# x50_brakelight.net
KiCad netlist of a schematic drawn in EAGLE
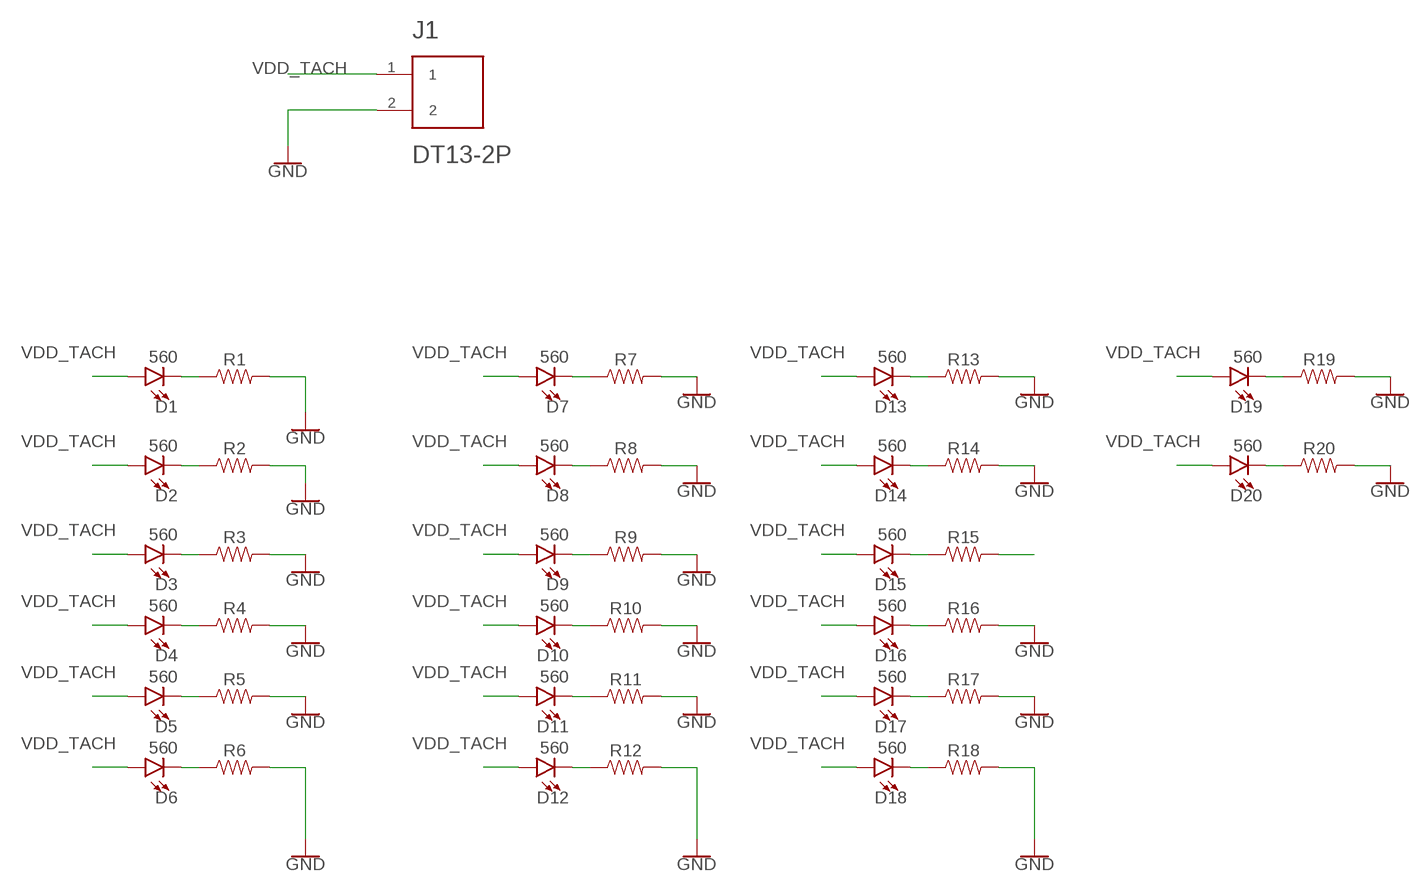
[diagram p0: schematic, sheet 1]

(export (version "E")
  (design (tool "Eeschema 10.0.6"))
  (components
    (comp (ref "D1")
      (value "560")
      (footprint "eagle-import:LED_5MM")
      (libsource (lib "eagle-import") (part "LED5MM"))
    )
    (comp (ref "D2")
      (value "560")
      (footprint "eagle-import:LED_5MM")
      (libsource (lib "eagle-import") (part "LED5MM"))
    )
    (comp (ref "D3")
      (value "560")
      (footprint "eagle-import:LED_5MM")
      (libsource (lib "eagle-import") (part "LED5MM"))
    )
    (comp (ref "D4")
      (value "560")
      (footprint "eagle-import:LED_5MM")
      (libsource (lib "eagle-import") (part "LED5MM"))
    )
    (comp (ref "D5")
      (value "560")
      (footprint "eagle-import:LED_5MM")
      (libsource (lib "eagle-import") (part "LED5MM"))
    )
    (comp (ref "D6")
      (value "560")
      (footprint "eagle-import:LED_5MM")
      (libsource (lib "eagle-import") (part "LED5MM"))
    )
    (comp (ref "D7")
      (value "560")
      (footprint "eagle-import:LED_5MM")
      (libsource (lib "eagle-import") (part "LED5MM"))
    )
    (comp (ref "D8")
      (value "560")
      (footprint "eagle-import:LED_5MM")
      (libsource (lib "eagle-import") (part "LED5MM"))
    )
    (comp (ref "D9")
      (value "560")
      (footprint "eagle-import:LED_5MM")
      (libsource (lib "eagle-import") (part "LED5MM"))
    )
    (comp (ref "D10")
      (value "560")
      (footprint "eagle-import:LED_5MM")
      (libsource (lib "eagle-import") (part "LED5MM"))
    )
    (comp (ref "D11")
      (value "560")
      (footprint "eagle-import:LED_5MM")
      (libsource (lib "eagle-import") (part "LED5MM"))
    )
    (comp (ref "D12")
      (value "560")
      (footprint "eagle-import:LED_5MM")
      (libsource (lib "eagle-import") (part "LED5MM"))
    )
    (comp (ref "D13")
      (value "560")
      (footprint "eagle-import:LED_5MM")
      (libsource (lib "eagle-import") (part "LED5MM"))
    )
    (comp (ref "D14")
      (value "560")
      (footprint "eagle-import:LED_5MM")
      (libsource (lib "eagle-import") (part "LED5MM"))
    )
    (comp (ref "D15")
      (value "560")
      (footprint "eagle-import:LED_5MM")
      (libsource (lib "eagle-import") (part "LED5MM"))
    )
    (comp (ref "D16")
      (value "560")
      (footprint "eagle-import:LED_5MM")
      (libsource (lib "eagle-import") (part "LED5MM"))
    )
    (comp (ref "D17")
      (value "560")
      (footprint "eagle-import:LED_5MM")
      (libsource (lib "eagle-import") (part "LED5MM"))
    )
    (comp (ref "D18")
      (value "560")
      (footprint "eagle-import:LED_5MM")
      (libsource (lib "eagle-import") (part "LED5MM"))
    )
    (comp (ref "D19")
      (value "560")
      (footprint "eagle-import:LED_5MM")
      (libsource (lib "eagle-import") (part "LED5MM"))
    )
    (comp (ref "D20")
      (value "560")
      (footprint "eagle-import:LED_5MM")
      (libsource (lib "eagle-import") (part "LED5MM"))
    )
    (comp (ref "J1")
      (value "DT13-2P")
      (footprint "eagle-import:TE_DT13-2P")
      (fields (field (name "MF") "TE Connectivity") (field (name "MPN") "DT13-2P "))
      (libsource (lib "eagle-import") (part "DT13-2P"))
    )
    (comp (ref "R1")
      (value "RESISTORAXIAL-0.3")
      (footprint "eagle-import:AXIAL-0.3")
      (libsource (lib "eagle-import") (part "RESISTORAXIAL-0.3"))
    )
    (comp (ref "R2")
      (value "RESISTORAXIAL-0.3")
      (footprint "eagle-import:AXIAL-0.3")
      (libsource (lib "eagle-import") (part "RESISTORAXIAL-0.3"))
    )
    (comp (ref "R3")
      (value "RESISTORAXIAL-0.3")
      (footprint "eagle-import:AXIAL-0.3")
      (libsource (lib "eagle-import") (part "RESISTORAXIAL-0.3"))
    )
    (comp (ref "R4")
      (value "RESISTORAXIAL-0.3")
      (footprint "eagle-import:AXIAL-0.3")
      (libsource (lib "eagle-import") (part "RESISTORAXIAL-0.3"))
    )
    (comp (ref "R5")
      (value "RESISTORAXIAL-0.3")
      (footprint "eagle-import:AXIAL-0.3")
      (libsource (lib "eagle-import") (part "RESISTORAXIAL-0.3"))
    )
    (comp (ref "R6")
      (value "RESISTORAXIAL-0.3")
      (footprint "eagle-import:AXIAL-0.3")
      (libsource (lib "eagle-import") (part "RESISTORAXIAL-0.3"))
    )
    (comp (ref "R7")
      (value "RESISTORAXIAL-0.3")
      (footprint "eagle-import:AXIAL-0.3")
      (libsource (lib "eagle-import") (part "RESISTORAXIAL-0.3"))
    )
    (comp (ref "R8")
      (value "RESISTORAXIAL-0.3")
      (footprint "eagle-import:AXIAL-0.3")
      (libsource (lib "eagle-import") (part "RESISTORAXIAL-0.3"))
    )
    (comp (ref "R9")
      (value "RESISTORAXIAL-0.3")
      (footprint "eagle-import:AXIAL-0.3")
      (libsource (lib "eagle-import") (part "RESISTORAXIAL-0.3"))
    )
    (comp (ref "R10")
      (value "RESISTORAXIAL-0.3")
      (footprint "eagle-import:AXIAL-0.3")
      (libsource (lib "eagle-import") (part "RESISTORAXIAL-0.3"))
    )
    (comp (ref "R11")
      (value "RESISTORAXIAL-0.3")
      (footprint "eagle-import:AXIAL-0.3")
      (libsource (lib "eagle-import") (part "RESISTORAXIAL-0.3"))
    )
    (comp (ref "R12")
      (value "RESISTORAXIAL-0.3")
      (footprint "eagle-import:AXIAL-0.3")
      (libsource (lib "eagle-import") (part "RESISTORAXIAL-0.3"))
    )
    (comp (ref "R13")
      (value "RESISTORAXIAL-0.3")
      (footprint "eagle-import:AXIAL-0.3")
      (libsource (lib "eagle-import") (part "RESISTORAXIAL-0.3"))
    )
    (comp (ref "R14")
      (value "RESISTORAXIAL-0.3")
      (footprint "eagle-import:AXIAL-0.3")
      (libsource (lib "eagle-import") (part "RESISTORAXIAL-0.3"))
    )
    (comp (ref "R15")
      (value "RESISTORAXIAL-0.3")
      (footprint "eagle-import:AXIAL-0.3")
      (libsource (lib "eagle-import") (part "RESISTORAXIAL-0.3"))
    )
    (comp (ref "R16")
      (value "RESISTORAXIAL-0.3")
      (footprint "eagle-import:AXIAL-0.3")
      (libsource (lib "eagle-import") (part "RESISTORAXIAL-0.3"))
    )
    (comp (ref "R17")
      (value "RESISTORAXIAL-0.3")
      (footprint "eagle-import:AXIAL-0.3")
      (libsource (lib "eagle-import") (part "RESISTORAXIAL-0.3"))
    )
    (comp (ref "R18")
      (value "RESISTORAXIAL-0.3")
      (footprint "eagle-import:AXIAL-0.3")
      (libsource (lib "eagle-import") (part "RESISTORAXIAL-0.3"))
    )
    (comp (ref "R19")
      (value "RESISTORAXIAL-0.3")
      (footprint "eagle-import:AXIAL-0.3")
      (libsource (lib "eagle-import") (part "RESISTORAXIAL-0.3"))
    )
    (comp (ref "R20")
      (value "RESISTORAXIAL-0.3")
      (footprint "eagle-import:AXIAL-0.3")
      (libsource (lib "eagle-import") (part "RESISTORAXIAL-0.3"))
    )
  )
  (nets
    (net (code "1") (name "/VDD_TACH") (class "Default")
      (node (ref "D1") (pin "A") (pinfunction "A_A") (pintype "passive"))
      (node (ref "D10") (pin "A") (pinfunction "A_A") (pintype "passive"))
      (node (ref "D11") (pin "A") (pinfunction "A_A") (pintype "passive"))
      (node (ref "D12") (pin "A") (pinfunction "A_A") (pintype "passive"))
      (node (ref "D13") (pin "A") (pinfunction "A_A") (pintype "passive"))
      (node (ref "D14") (pin "A") (pinfunction "A_A") (pintype "passive"))
      (node (ref "D15") (pin "A") (pinfunction "A_A") (pintype "passive"))
      (node (ref "D16") (pin "A") (pinfunction "A_A") (pintype "passive"))
      (node (ref "D17") (pin "A") (pinfunction "A_A") (pintype "passive"))
      (node (ref "D18") (pin "A") (pinfunction "A_A") (pintype "passive"))
      (node (ref "D19") (pin "A") (pinfunction "A_A") (pintype "passive"))
      (node (ref "D2") (pin "A") (pinfunction "A_A") (pintype "passive"))
      (node (ref "D20") (pin "A") (pinfunction "A_A") (pintype "passive"))
      (node (ref "D3") (pin "A") (pinfunction "A_A") (pintype "passive"))
      (node (ref "D4") (pin "A") (pinfunction "A_A") (pintype "passive"))
      (node (ref "D5") (pin "A") (pinfunction "A_A") (pintype "passive"))
      (node (ref "D6") (pin "A") (pinfunction "A_A") (pintype "passive"))
      (node (ref "D7") (pin "A") (pinfunction "A_A") (pintype "passive"))
      (node (ref "D8") (pin "A") (pinfunction "A_A") (pintype "passive"))
      (node (ref "D9") (pin "A") (pinfunction "A_A") (pintype "passive"))
      (node (ref "J1") (pin "1") (pinfunction "1_1") (pintype "passive"))
    )
    (net (code "2") (name "GND") (class "Default")
      (node (ref "J1") (pin "2") (pinfunction "2_2") (pintype "passive"))
      (node (ref "R1") (pin "P$2") (pinfunction "2_P$2") (pintype "passive"))
      (node (ref "R10") (pin "P$2") (pinfunction "2_P$2") (pintype "passive"))
      (node (ref "R11") (pin "P$2") (pinfunction "2_P$2") (pintype "passive"))
      (node (ref "R12") (pin "P$2") (pinfunction "2_P$2") (pintype "passive"))
      (node (ref "R13") (pin "P$2") (pinfunction "2_P$2") (pintype "passive"))
      (node (ref "R14") (pin "P$2") (pinfunction "2_P$2") (pintype "passive"))
      (node (ref "R16") (pin "P$2") (pinfunction "2_P$2") (pintype "passive"))
      (node (ref "R17") (pin "P$2") (pinfunction "2_P$2") (pintype "passive"))
      (node (ref "R18") (pin "P$2") (pinfunction "2_P$2") (pintype "passive"))
      (node (ref "R19") (pin "P$2") (pinfunction "2_P$2") (pintype "passive"))
      (node (ref "R2") (pin "P$2") (pinfunction "2_P$2") (pintype "passive"))
      (node (ref "R20") (pin "P$2") (pinfunction "2_P$2") (pintype "passive"))
      (node (ref "R3") (pin "P$2") (pinfunction "2_P$2") (pintype "passive"))
      (node (ref "R4") (pin "P$2") (pinfunction "2_P$2") (pintype "passive"))
      (node (ref "R5") (pin "P$2") (pinfunction "2_P$2") (pintype "passive"))
      (node (ref "R6") (pin "P$2") (pinfunction "2_P$2") (pintype "passive"))
      (node (ref "R7") (pin "P$2") (pinfunction "2_P$2") (pintype "passive"))
      (node (ref "R8") (pin "P$2") (pinfunction "2_P$2") (pintype "passive"))
      (node (ref "R9") (pin "P$2") (pinfunction "2_P$2") (pintype "passive"))
    )
    (net (code "3") (name "Net-(D1-C)") (class "Default")
      (node (ref "D1") (pin "K") (pinfunction "C_K") (pintype "passive"))
      (node (ref "R1") (pin "P$1") (pinfunction "1_P$1") (pintype "passive"))
    )
    (net (code "4") (name "Net-(D2-C)") (class "Default")
      (node (ref "D2") (pin "K") (pinfunction "C_K") (pintype "passive"))
      (node (ref "R2") (pin "P$1") (pinfunction "1_P$1") (pintype "passive"))
    )
    (net (code "5") (name "Net-(D3-C)") (class "Default")
      (node (ref "D3") (pin "K") (pinfunction "C_K") (pintype "passive"))
      (node (ref "R3") (pin "P$1") (pinfunction "1_P$1") (pintype "passive"))
    )
    (net (code "6") (name "Net-(D4-C)") (class "Default")
      (node (ref "D4") (pin "K") (pinfunction "C_K") (pintype "passive"))
      (node (ref "R4") (pin "P$1") (pinfunction "1_P$1") (pintype "passive"))
    )
    (net (code "7") (name "Net-(D5-C)") (class "Default")
      (node (ref "D5") (pin "K") (pinfunction "C_K") (pintype "passive"))
      (node (ref "R5") (pin "P$1") (pinfunction "1_P$1") (pintype "passive"))
    )
    (net (code "8") (name "Net-(D6-C)") (class "Default")
      (node (ref "D6") (pin "K") (pinfunction "C_K") (pintype "passive"))
      (node (ref "R6") (pin "P$1") (pinfunction "1_P$1") (pintype "passive"))
    )
    (net (code "9") (name "Net-(D7-C)") (class "Default")
      (node (ref "D7") (pin "K") (pinfunction "C_K") (pintype "passive"))
      (node (ref "R7") (pin "P$1") (pinfunction "1_P$1") (pintype "passive"))
    )
    (net (code "10") (name "Net-(D8-C)") (class "Default")
      (node (ref "D8") (pin "K") (pinfunction "C_K") (pintype "passive"))
      (node (ref "R8") (pin "P$1") (pinfunction "1_P$1") (pintype "passive"))
    )
    (net (code "11") (name "Net-(D9-C)") (class "Default")
      (node (ref "D9") (pin "K") (pinfunction "C_K") (pintype "passive"))
      (node (ref "R9") (pin "P$1") (pinfunction "1_P$1") (pintype "passive"))
    )
    (net (code "12") (name "Net-(D10-C)") (class "Default")
      (node (ref "D10") (pin "K") (pinfunction "C_K") (pintype "passive"))
      (node (ref "R10") (pin "P$1") (pinfunction "1_P$1") (pintype "passive"))
    )
    (net (code "13") (name "Net-(D11-C)") (class "Default")
      (node (ref "D11") (pin "K") (pinfunction "C_K") (pintype "passive"))
      (node (ref "R11") (pin "P$1") (pinfunction "1_P$1") (pintype "passive"))
    )
    (net (code "14") (name "Net-(D12-C)") (class "Default")
      (node (ref "D12") (pin "K") (pinfunction "C_K") (pintype "passive"))
      (node (ref "R12") (pin "P$1") (pinfunction "1_P$1") (pintype "passive"))
    )
    (net (code "15") (name "Net-(D13-C)") (class "Default")
      (node (ref "D13") (pin "K") (pinfunction "C_K") (pintype "passive"))
      (node (ref "R13") (pin "P$1") (pinfunction "1_P$1") (pintype "passive"))
    )
    (net (code "16") (name "Net-(D14-C)") (class "Default")
      (node (ref "D14") (pin "K") (pinfunction "C_K") (pintype "passive"))
      (node (ref "R14") (pin "P$1") (pinfunction "1_P$1") (pintype "passive"))
    )
    (net (code "17") (name "Net-(D15-C)") (class "Default")
      (node (ref "D15") (pin "K") (pinfunction "C_K") (pintype "passive"))
      (node (ref "R15") (pin "P$1") (pinfunction "1_P$1") (pintype "passive"))
    )
    (net (code "18") (name "Net-(D16-C)") (class "Default")
      (node (ref "D16") (pin "K") (pinfunction "C_K") (pintype "passive"))
      (node (ref "R16") (pin "P$1") (pinfunction "1_P$1") (pintype "passive"))
    )
    (net (code "19") (name "Net-(D17-C)") (class "Default")
      (node (ref "D17") (pin "K") (pinfunction "C_K") (pintype "passive"))
      (node (ref "R17") (pin "P$1") (pinfunction "1_P$1") (pintype "passive"))
    )
    (net (code "20") (name "Net-(D18-C)") (class "Default")
      (node (ref "D18") (pin "K") (pinfunction "C_K") (pintype "passive"))
      (node (ref "R18") (pin "P$1") (pinfunction "1_P$1") (pintype "passive"))
    )
    (net (code "21") (name "Net-(D19-C)") (class "Default")
      (node (ref "D19") (pin "K") (pinfunction "C_K") (pintype "passive"))
      (node (ref "R19") (pin "P$1") (pinfunction "1_P$1") (pintype "passive"))
    )
    (net (code "22") (name "Net-(D20-C)") (class "Default")
      (node (ref "D20") (pin "K") (pinfunction "C_K") (pintype "passive"))
      (node (ref "R20") (pin "P$1") (pinfunction "1_P$1") (pintype "passive"))
    )
    (net (code "23") (name "unconnected-(R15-2-PadP$2)") (class "Default")
      (node (ref "R15") (pin "P$2") (pinfunction "2_P$2") (pintype "passive"))
    )
  )
)
